# EstacionESP8266_v1.net
KiCad netlist of a schematic drawn in EAGLE
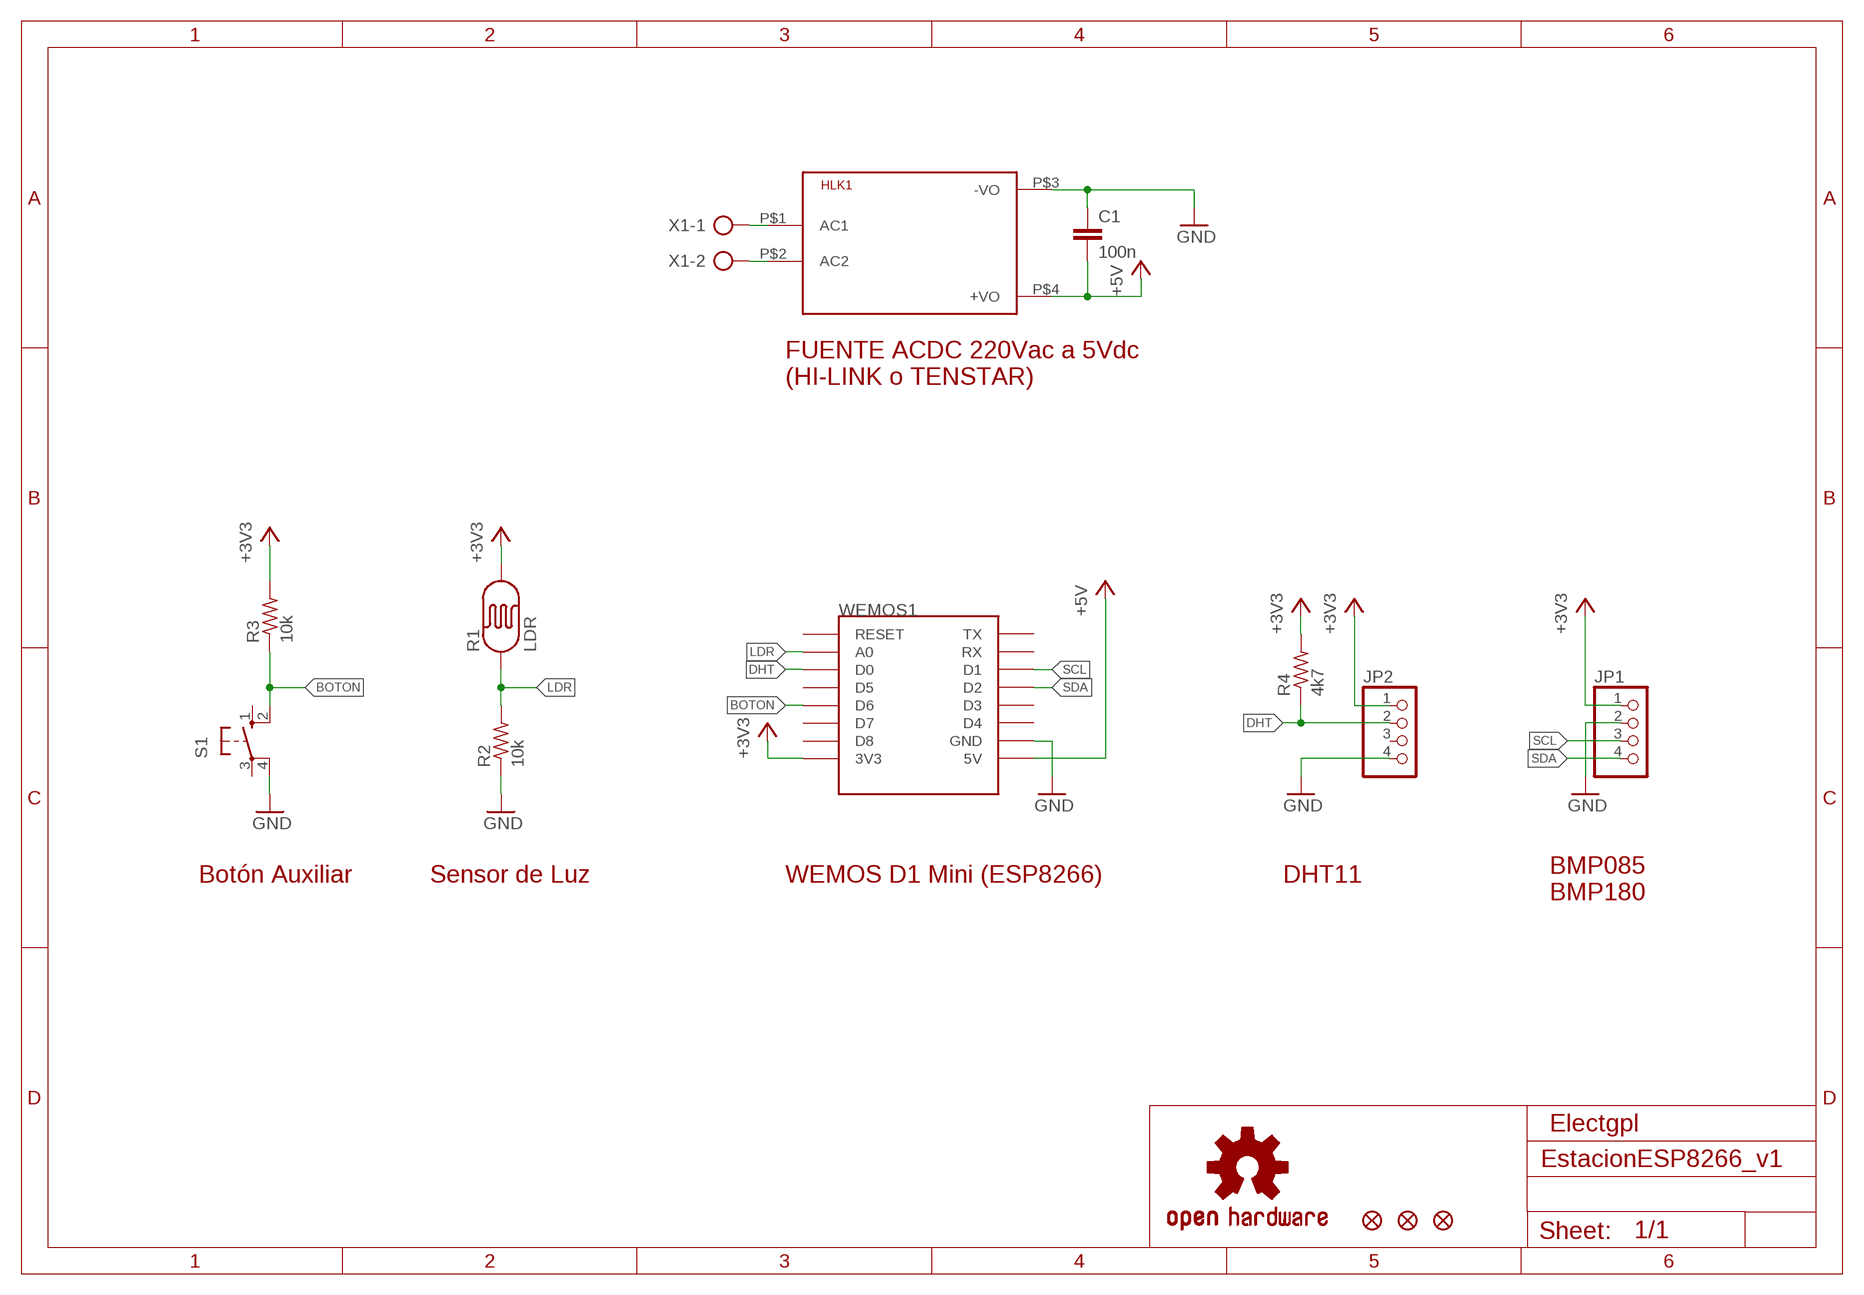
[diagram p0: schematic, sheet 1]

(export (version "E")
  (design (tool "Eeschema 10.0.6"))
  (components
    (comp (ref "C1")
      (value "100n")
      (footprint "eagle-import:C050-024X044")
      (libsource (lib "eagle-import") (part "C-EU050-024X044"))
    )
    (comp (ref "HLK1")
      (value "HLK-PM013W")
      (footprint "eagle-import:HLK-PM01")
      (libsource (lib "eagle-import") (part "HLK-PM013W"))
    )
    (comp (ref "JP1")
      (value "PINHD-1X4")
      (footprint "eagle-import:1X04")
      (libsource (lib "eagle-import") (part "PINHD-1X4"))
    )
    (comp (ref "JP2")
      (value "PINHD-1X4")
      (footprint "eagle-import:1X04")
      (libsource (lib "eagle-import") (part "PINHD-1X4"))
    )
    (comp (ref "JP3")
      (value "FIDUCIAL1.5X3")
      (footprint "eagle-import:FIDUCIAL-1.5X3")
      (libsource (lib "eagle-import") (part "FIDUCIAL1.5X3"))
    )
    (comp (ref "JP4")
      (value "FIDUCIAL1.5X3")
      (footprint "eagle-import:FIDUCIAL-1.5X3")
      (libsource (lib "eagle-import") (part "FIDUCIAL1.5X3"))
    )
    (comp (ref "JP5")
      (value "FIDUCIAL1.5X3")
      (footprint "eagle-import:FIDUCIAL-1.5X3")
      (libsource (lib "eagle-import") (part "FIDUCIAL1.5X3"))
    )
    (comp (ref "R1")
      (value "LDR")
      (footprint "eagle-import:PHOTOCELL")
      (libsource (lib "eagle-import") (part "PHOTOCELLPTH"))
    )
    (comp (ref "R2")
      (value "10k")
      (footprint "eagle-import:0204_7")
      (libsource (lib "eagle-import") (part "R-US_0204/7"))
    )
    (comp (ref "R3")
      (value "10k")
      (footprint "eagle-import:0204_7")
      (libsource (lib "eagle-import") (part "R-US_0204/7"))
    )
    (comp (ref "R4")
      (value "4k7")
      (footprint "eagle-import:0204_7")
      (libsource (lib "eagle-import") (part "R-US_0204/7"))
    )
    (comp (ref "S1")
      (value "10-XX")
      (footprint "eagle-import:B3F-10XX")
      (fields (field (name "MPN") "B3F-1000"))
      (libsource (lib "eagle-import") (part "10-XX"))
    )
    (comp (ref "U$5")
      (value "OSHW-LOGOM")
      (footprint "eagle-import:OSHW-LOGO-M")
      (libsource (lib "eagle-import") (part "OSHW-LOGOM"))
    )
    (comp (ref "WEMOS1")
      (value "WEMOS-D1-MINI")
      (footprint "eagle-import:WEMOS-D1-MINI")
      (libsource (lib "eagle-import") (part "WEMOS-D1-MINI"))
    )
    (comp (ref "X1")
      (value "AK500/2")
      (footprint "eagle-import:AK500_2")
      (libsource (lib "eagle-import") (part "AK500/2"))
    )
  )
  (nets
    (net (code "1") (name "+3V3") (class "Default")
      (node (ref "JP1") (pin "1") (pinfunction "1_1") (pintype "passive"))
      (node (ref "JP2") (pin "1") (pinfunction "1_1") (pintype "passive"))
      (node (ref "R1") (pin "2") (pinfunction "P$2_2") (pintype "bidirectional"))
      (node (ref "R3") (pin "2") (pinfunction "2_2") (pintype "passive"))
      (node (ref "R4") (pin "2") (pinfunction "2_2") (pintype "passive"))
      (node (ref "WEMOS1") (pin "3V3") (pinfunction "3V3_3V3") (pintype "bidirectional"))
    )
    (net (code "2") (name "+5V") (class "Default")
      (node (ref "C1") (pin "2") (pinfunction "2_2") (pintype "passive"))
      (node (ref "HLK1") (pin "P$4") (pinfunction "+VO_P$4") (pintype "bidirectional"))
      (node (ref "WEMOS1") (pin "5V") (pinfunction "5V_5V") (pintype "bidirectional"))
    )
    (net (code "3") (name "BOTON") (class "Default")
      (node (ref "R3") (pin "1") (pinfunction "1_1") (pintype "passive"))
      (node (ref "S1") (pin "2") (pinfunction "S1_2") (pintype "passive"))
      (node (ref "WEMOS1") (pin "D6") (pinfunction "D6_D6") (pintype "bidirectional"))
    )
    (net (code "4") (name "DHT") (class "Default")
      (node (ref "JP2") (pin "2") (pinfunction "2_2") (pintype "passive"))
      (node (ref "R4") (pin "1") (pinfunction "1_1") (pintype "passive"))
      (node (ref "WEMOS1") (pin "D0") (pinfunction "D0_D0") (pintype "bidirectional"))
    )
    (net (code "5") (name "GND") (class "Default")
      (node (ref "C1") (pin "1") (pinfunction "1_1") (pintype "passive"))
      (node (ref "HLK1") (pin "P$3") (pinfunction "-VO_P$3") (pintype "bidirectional"))
      (node (ref "JP1") (pin "2") (pinfunction "2_2") (pintype "passive"))
      (node (ref "JP2") (pin "4") (pinfunction "4_4") (pintype "passive"))
      (node (ref "R2") (pin "1") (pinfunction "1_1") (pintype "passive"))
      (node (ref "S1") (pin "4") (pinfunction "P1_4") (pintype "passive"))
      (node (ref "WEMOS1") (pin "GND") (pinfunction "GND_GND") (pintype "bidirectional"))
    )
    (net (code "6") (name "LDR") (class "Default")
      (node (ref "R1") (pin "1") (pinfunction "P$1_1") (pintype "bidirectional"))
      (node (ref "R2") (pin "2") (pinfunction "2_2") (pintype "passive"))
      (node (ref "WEMOS1") (pin "A0") (pinfunction "A0_A0") (pintype "bidirectional"))
    )
    (net (code "7") (name "Net-(HLK1-AC1)") (class "Default")
      (node (ref "HLK1") (pin "P$1") (pinfunction "AC1_P$1") (pintype "bidirectional"))
      (node (ref "X1") (pin "1") (pinfunction "KL_1") (pintype "passive"))
    )
    (net (code "8") (name "Net-(HLK1-AC2)") (class "Default")
      (node (ref "HLK1") (pin "P$2") (pinfunction "AC2_P$2") (pintype "bidirectional"))
      (node (ref "X1") (pin "2") (pinfunction "KL_2") (pintype "passive"))
    )
    (net (code "9") (name "SCL") (class "Default")
      (node (ref "JP1") (pin "3") (pinfunction "3_3") (pintype "passive"))
      (node (ref "WEMOS1") (pin "D1") (pinfunction "D1_D1") (pintype "bidirectional"))
    )
    (net (code "10") (name "SDA") (class "Default")
      (node (ref "JP1") (pin "4") (pinfunction "4_4") (pintype "passive"))
      (node (ref "WEMOS1") (pin "D2") (pinfunction "D2_D2") (pintype "bidirectional"))
    )
    (net (code "11") (name "unconnected-(JP2-Pad3)") (class "Default")
      (node (ref "JP2") (pin "3") (pinfunction "3_3") (pintype "passive"))
    )
    (net (code "12") (name "unconnected-(S1-P-Pad3)") (class "Default")
      (node (ref "S1") (pin "3") (pinfunction "P_3") (pintype "passive"))
    )
    (net (code "13") (name "unconnected-(S1-S-Pad1)") (class "Default")
      (node (ref "S1") (pin "1") (pinfunction "S_1") (pintype "passive"))
    )
    (net (code "14") (name "unconnected-(WEMOS1-PadD3)") (class "Default")
      (node (ref "WEMOS1") (pin "D3") (pinfunction "D3_D3") (pintype "bidirectional"))
    )
    (net (code "15") (name "unconnected-(WEMOS1-PadD4)") (class "Default")
      (node (ref "WEMOS1") (pin "D4") (pinfunction "D4_D4") (pintype "bidirectional"))
    )
    (net (code "16") (name "unconnected-(WEMOS1-PadD5)") (class "Default")
      (node (ref "WEMOS1") (pin "D5") (pinfunction "D5_D5") (pintype "bidirectional"))
    )
    (net (code "17") (name "unconnected-(WEMOS1-PadD7)") (class "Default")
      (node (ref "WEMOS1") (pin "D7") (pinfunction "D7_D7") (pintype "bidirectional"))
    )
    (net (code "18") (name "unconnected-(WEMOS1-PadD8)") (class "Default")
      (node (ref "WEMOS1") (pin "D8") (pinfunction "D8_D8") (pintype "bidirectional"))
    )
    (net (code "19") (name "unconnected-(WEMOS1-PadRESET)") (class "Default")
      (node (ref "WEMOS1") (pin "RESET") (pinfunction "RESET_RESET") (pintype "bidirectional"))
    )
    (net (code "20") (name "unconnected-(WEMOS1-PadRX)") (class "Default")
      (node (ref "WEMOS1") (pin "RX") (pinfunction "RX_RX") (pintype "bidirectional"))
    )
    (net (code "21") (name "unconnected-(WEMOS1-PadTX)") (class "Default")
      (node (ref "WEMOS1") (pin "TX") (pinfunction "TX_TX") (pintype "bidirectional"))
    )
  )
)
